# Power_supply.net
KiCad netlist of a schematic drawn in Altium Designer
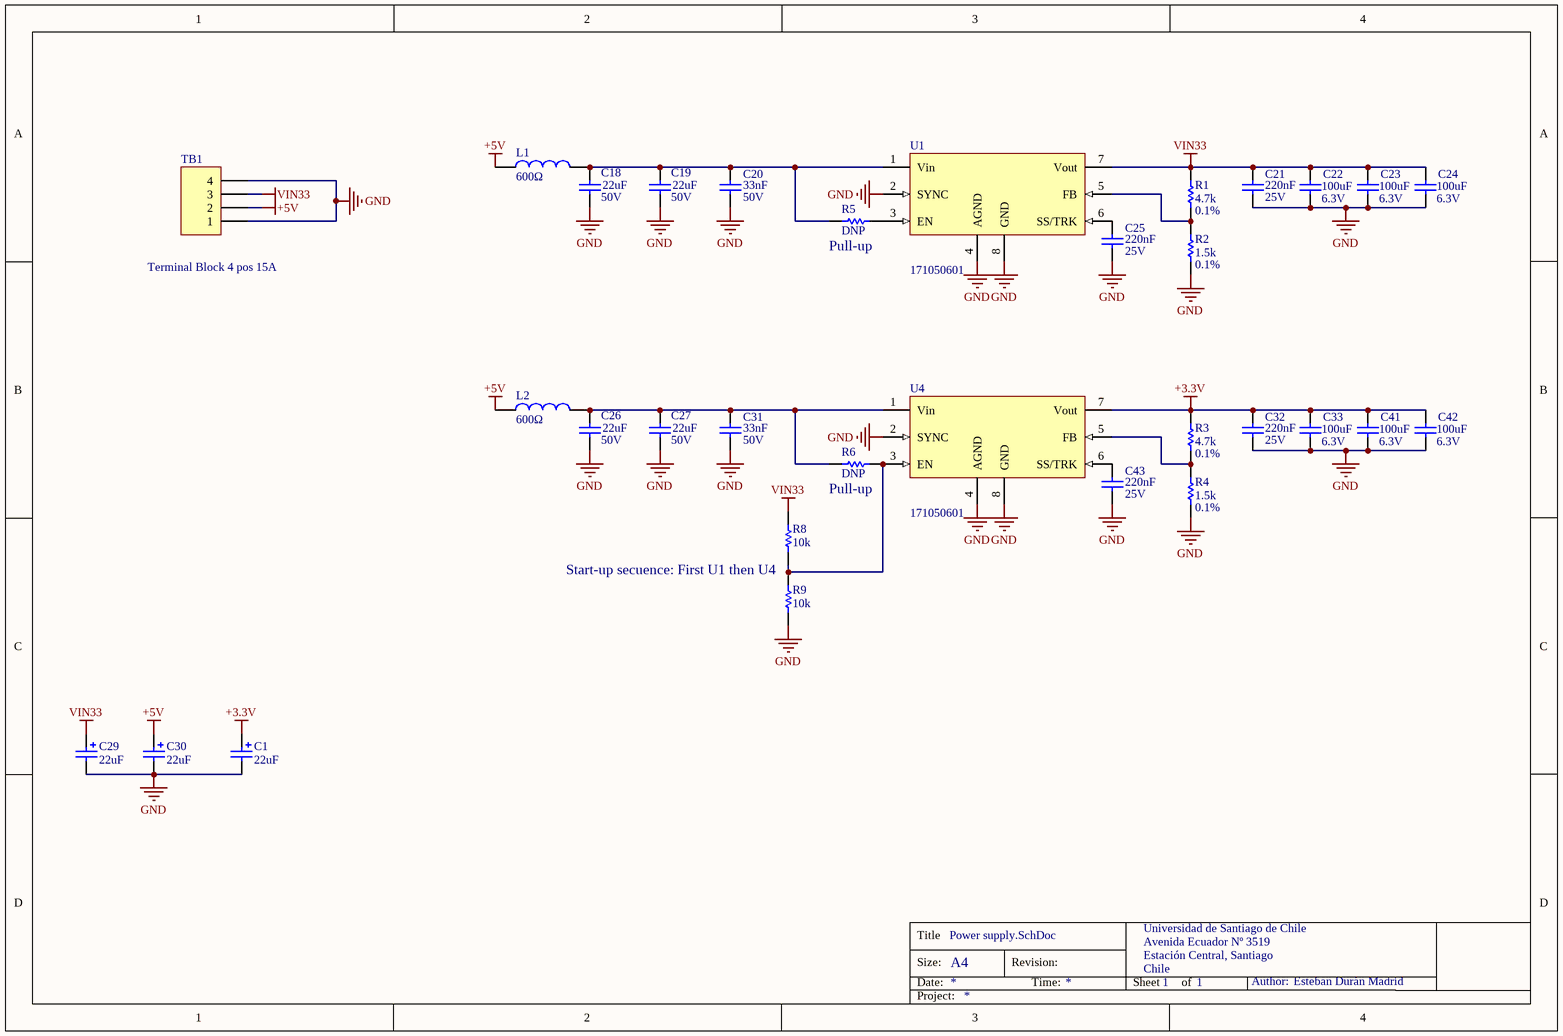
[diagram p0: Power supply.SchDoc]

(export (version "E")
  (design (tool "Eeschema 10.0.6"))
  (components
    (comp (ref "C1")
      (value "22uF")
      (footprint "CAP Electrolítico Radial SMD2")
      (description "Polarized Capacitor (Radial)")
      (fields (field (name "PUBLISHER") "Altium Limited"))
      (libsource (lib "Componentes_SOC") (part "Cap Pol"))
    )
    (comp (ref "C18")
      (value "22uF")
      (footprint "RES_1206")
      (description "Capacitor")
      (fields (field (name "VOLTAGE") "50V") (field (name "PUBLISHER") "Altium Limited"))
      (libsource (lib "Componentes_SOC") (part "Cap_1206"))
    )
    (comp (ref "C19")
      (value "22uF")
      (footprint "RES_1206")
      (description "Capacitor")
      (fields (field (name "VOLTAGE") "50V") (field (name "PUBLISHER") "Altium Limited"))
      (libsource (lib "Componentes_SOC") (part "Cap_1206"))
    )
    (comp (ref "C20")
      (value "33nF")
      (footprint "CAP_0603")
      (description "Capacitor")
      (fields (field (name "VOLTAGE") "50V") (field (name "PUBLISHER") "Altium Limited"))
      (libsource (lib "Componentes_SOC") (part "Cap_0603"))
    )
    (comp (ref "C21")
      (value "220nF")
      (footprint "CAP_0603")
      (description "Capacitor")
      (fields (field (name "VOLTAGE") "25V") (field (name "PUBLISHER") "Altium Limited"))
      (libsource (lib "Componentes_SOC") (part "Cap_0603"))
    )
    (comp (ref "C22")
      (value "100uF")
      (footprint "Cap_1210")
      (description "Capacitor")
      (fields (field (name "VOLTAGE") "6.3V") (field (name "PUBLISHER") "Altium Limited"))
      (libsource (lib "Componentes_SOC") (part "Cap_1210"))
    )
    (comp (ref "C23")
      (value "100uF")
      (footprint "Cap_1210")
      (description "Capacitor")
      (fields (field (name "VOLTAGE") "6.3V") (field (name "PUBLISHER") "Altium Limited"))
      (libsource (lib "Componentes_SOC") (part "Cap_1210"))
    )
    (comp (ref "C24")
      (value "100uF")
      (footprint "Cap_1210")
      (description "Capacitor")
      (fields (field (name "VOLTAGE") "6.3V") (field (name "PUBLISHER") "Altium Limited"))
      (libsource (lib "Componentes_SOC") (part "Cap_1210"))
    )
    (comp (ref "C25")
      (value "220nF")
      (footprint "CAP_0603")
      (description "Capacitor")
      (fields (field (name "VOLTAGE") "25V") (field (name "PUBLISHER") "Altium Limited"))
      (libsource (lib "Componentes_SOC") (part "Cap_0603"))
    )
    (comp (ref "C26")
      (value "22uF")
      (footprint "RES_1206")
      (description "Capacitor")
      (fields (field (name "VOLTAGE") "50V") (field (name "PUBLISHER") "Altium Limited"))
      (libsource (lib "Componentes_SOC") (part "Cap_1206"))
    )
    (comp (ref "C27")
      (value "22uF")
      (footprint "RES_1206")
      (description "Capacitor")
      (fields (field (name "VOLTAGE") "50V") (field (name "PUBLISHER") "Altium Limited"))
      (libsource (lib "Componentes_SOC") (part "Cap_1206"))
    )
    (comp (ref "C29")
      (value "22uF")
      (footprint "CAP Electrolítico Radial SMD2")
      (description "Polarized Capacitor (Radial)")
      (fields (field (name "PUBLISHER") "Altium Limited"))
      (libsource (lib "Componentes_SOC") (part "Cap Pol"))
    )
    (comp (ref "C30")
      (value "22uF")
      (footprint "CAP Electrolítico Radial SMD2")
      (description "Polarized Capacitor (Radial)")
      (fields (field (name "PUBLISHER") "Altium Limited"))
      (libsource (lib "Componentes_SOC") (part "Cap Pol"))
    )
    (comp (ref "C31")
      (value "33nF")
      (footprint "CAP_0603")
      (description "Capacitor")
      (fields (field (name "VOLTAGE") "50V") (field (name "PUBLISHER") "Altium Limited"))
      (libsource (lib "Componentes_SOC") (part "Cap_0603"))
    )
    (comp (ref "C32")
      (value "220nF")
      (footprint "CAP_0603")
      (description "Capacitor")
      (fields (field (name "VOLTAGE") "25V") (field (name "PUBLISHER") "Altium Limited"))
      (libsource (lib "Componentes_SOC") (part "Cap_0603"))
    )
    (comp (ref "C33")
      (value "100uF")
      (footprint "Cap_1210")
      (description "Capacitor")
      (fields (field (name "VOLTAGE") "6.3V") (field (name "PUBLISHER") "Altium Limited"))
      (libsource (lib "Componentes_SOC") (part "Cap_1210"))
    )
    (comp (ref "C41")
      (value "100uF")
      (footprint "Cap_1210")
      (description "Capacitor")
      (fields (field (name "VOLTAGE") "6.3V") (field (name "PUBLISHER") "Altium Limited"))
      (libsource (lib "Componentes_SOC") (part "Cap_1210"))
    )
    (comp (ref "C42")
      (value "100uF")
      (footprint "Cap_1210")
      (description "Capacitor")
      (fields (field (name "VOLTAGE") "6.3V") (field (name "PUBLISHER") "Altium Limited"))
      (libsource (lib "Componentes_SOC") (part "Cap_1210"))
    )
    (comp (ref "C43")
      (value "220nF")
      (footprint "CAP_0603")
      (description "Capacitor")
      (fields (field (name "VOLTAGE") "25V") (field (name "PUBLISHER") "Altium Limited"))
      (libsource (lib "Componentes_SOC") (part "Cap_0603"))
    )
    (comp (ref "L1")
      (value "600Ω")
      (footprint "WE-CBF_0805_High Current")
      (description "WE-CBF SMD EMI Suppression Ferrite Bead, 0805, 600Ω")
      (fields
        (field (name "PARTNUMBER") "742792040")
        (field (name "PUBLISHER") "Wurth Elektronik")
        (field (name "CREATED") "2018_09_11_AGeiger")
      )
      (libsource (lib "UltraZOhm_CarrierBoard_1v1") (part "WE-CBF, 742792040"))
    )
    (comp (ref "L2")
      (value "600Ω")
      (footprint "WE-CBF_0805_High Current")
      (description "WE-CBF SMD EMI Suppression Ferrite Bead, 0805, 600Ω")
      (fields
        (field (name "PARTNUMBER") "742792040")
        (field (name "PUBLISHER") "Wurth Elektronik")
        (field (name "CREATED") "2018_09_11_AGeiger")
      )
      (libsource (lib "UltraZOhm_CarrierBoard_1v1") (part "WE-CBF, 742792040"))
    )
    (comp (ref "R1")
      (value "4.7k")
      (footprint "RES_0603")
      (fields (field (name "TOLERANCE") "0.1%") (field (name "PUBLISHER") "Altium Limited"))
      (libsource (lib "Componentes_SOC") (part "Res0603"))
    )
    (comp (ref "R2")
      (value "1.5k")
      (footprint "RES_0603")
      (fields (field (name "TOLERANCE") "0.1%") (field (name "PUBLISHER") "Altium Limited"))
      (libsource (lib "Componentes_SOC") (part "Res0603"))
    )
    (comp (ref "R3")
      (value "4.7k")
      (footprint "RES_0603")
      (fields (field (name "TOLERANCE") "0.1%") (field (name "PUBLISHER") "Altium Limited"))
      (libsource (lib "Componentes_SOC") (part "Res0603"))
    )
    (comp (ref "R4")
      (value "1.5k")
      (footprint "RES_0603")
      (fields (field (name "TOLERANCE") "0.1%") (field (name "PUBLISHER") "Altium Limited"))
      (libsource (lib "Componentes_SOC") (part "Res0603"))
    )
    (comp (ref "R5")
      (value "DNP")
      (footprint "RES_0603")
      (fields (field (name "PUBLISHER") "Altium Limited"))
      (libsource (lib "Componentes_SOC") (part "Res0603"))
    )
    (comp (ref "R6")
      (value "DNP")
      (footprint "RES_0603")
      (fields (field (name "PUBLISHER") "Altium Limited"))
      (libsource (lib "Componentes_SOC") (part "Res0603"))
    )
    (comp (ref "R8")
      (value "10k")
      (footprint "RES_0603")
      (fields (field (name "PUBLISHER") "Altium Limited"))
      (libsource (lib "Componentes_SOC") (part "Res0603"))
    )
    (comp (ref "R9")
      (value "10k")
      (footprint "RES_0603")
      (fields (field (name "PUBLISHER") "Altium Limited"))
      (libsource (lib "Componentes_SOC") (part "Res0603"))
    )
    (comp (ref "TB1")
      (value "Terminal Block 4 pos 15A")
      (footprint "Terminal Block 4 pos 15A")
      (description "Molex Through Hole")
      (fields (field (name "PUBLISHER") "Altium Limited"))
      (libsource (lib "Componentes_SOC") (part "Terminal Block 4 pos 15A"))
    )
    (comp (ref "U1")
      (value "171050601")
      (footprint "7TO-PMOD")
      (description "DC/DC VIN = 6V-36V, 5A, VOUT = 0.8V-6V")
      (fields (field (name "MANUFACTURER") "Wuerth Elektronik") (field (name "CREATED") "2018_09_06_AGeiger"))
      (libsource (lib "UltraZOhm_CarrierBoard_1v1") (part "WE-DCDC-171050601"))
    )
    (comp (ref "U4")
      (value "171050601")
      (footprint "7TO-PMOD")
      (description "DC/DC VIN = 6V-36V, 5A, VOUT = 0.8V-6V")
      (fields (field (name "MANUFACTURER") "Wuerth Elektronik") (field (name "CREATED") "2018_09_06_AGeiger"))
      (libsource (lib "UltraZOhm_CarrierBoard_1v1") (part "WE-DCDC-171050601"))
    )
  )
  (nets
    (net (code "1") (name "+3.3V") (class "Default")
      (node (ref "C1") (pin "1") (pinfunction "1_1") (pintype "passive"))
      (node (ref "C32") (pin "1") (pinfunction "1_1") (pintype "passive"))
      (node (ref "C33") (pin "1") (pinfunction "1_1") (pintype "passive"))
      (node (ref "C41") (pin "1") (pinfunction "1_1") (pintype "passive"))
      (node (ref "C42") (pin "1") (pinfunction "1_1") (pintype "passive"))
      (node (ref "R3") (pin "2") (pinfunction "2_2") (pintype "passive"))
      (node (ref "U4") (pin "7") (pinfunction "Vout_7") (pintype "power_in"))
    )
    (net (code "2") (name "+5V") (class "Default")
      (node (ref "C30") (pin "1") (pinfunction "1_1") (pintype "passive"))
      (node (ref "L1") (pin "1") (pinfunction "1_1") (pintype "passive"))
      (node (ref "L2") (pin "1") (pinfunction "1_1") (pintype "passive"))
      (node (ref "TB1") (pin "2") (pinfunction "2_2") (pintype "passive"))
    )
    (net (code "3") (name "GND") (class "Default")
      (node (ref "C1") (pin "2") (pinfunction "2_2") (pintype "passive"))
      (node (ref "C18") (pin "2") (pinfunction "2_2") (pintype "passive"))
      (node (ref "C19") (pin "2") (pinfunction "2_2") (pintype "passive"))
      (node (ref "C20") (pin "2") (pinfunction "2_2") (pintype "passive"))
      (node (ref "C21") (pin "2") (pinfunction "2_2") (pintype "passive"))
      (node (ref "C22") (pin "2") (pinfunction "2_2") (pintype "passive"))
      (node (ref "C23") (pin "2") (pinfunction "2_2") (pintype "passive"))
      (node (ref "C24") (pin "2") (pinfunction "2_2") (pintype "passive"))
      (node (ref "C25") (pin "2") (pinfunction "2_2") (pintype "passive"))
      (node (ref "C26") (pin "2") (pinfunction "2_2") (pintype "passive"))
      (node (ref "C27") (pin "2") (pinfunction "2_2") (pintype "passive"))
      (node (ref "C29") (pin "2") (pinfunction "2_2") (pintype "passive"))
      (node (ref "C30") (pin "2") (pinfunction "2_2") (pintype "passive"))
      (node (ref "C31") (pin "2") (pinfunction "2_2") (pintype "passive"))
      (node (ref "C32") (pin "2") (pinfunction "2_2") (pintype "passive"))
      (node (ref "C33") (pin "2") (pinfunction "2_2") (pintype "passive"))
      (node (ref "C41") (pin "2") (pinfunction "2_2") (pintype "passive"))
      (node (ref "C42") (pin "2") (pinfunction "2_2") (pintype "passive"))
      (node (ref "C43") (pin "2") (pinfunction "2_2") (pintype "passive"))
      (node (ref "R2") (pin "1") (pinfunction "1_1") (pintype "passive"))
      (node (ref "R4") (pin "1") (pinfunction "1_1") (pintype "passive"))
      (node (ref "R9") (pin "1") (pinfunction "1_1") (pintype "passive"))
      (node (ref "TB1") (pin "1") (pinfunction "1_1") (pintype "passive"))
      (node (ref "TB1") (pin "4") (pinfunction "4_4") (pintype "passive"))
      (node (ref "U1") (pin "2") (pinfunction "SYNC_2") (pintype "input"))
      (node (ref "U1") (pin "4") (pinfunction "AGND_4") (pintype "power_in"))
      (node (ref "U1") (pin "8") (pinfunction "GND_8") (pintype "power_in"))
      (node (ref "U4") (pin "2") (pinfunction "SYNC_2") (pintype "input"))
      (node (ref "U4") (pin "4") (pinfunction "AGND_4") (pintype "power_in"))
      (node (ref "U4") (pin "8") (pinfunction "GND_8") (pintype "power_in"))
    )
    (net (code "4") (name "Net-(U1-EN)") (class "Default")
      (node (ref "R5") (pin "1") (pinfunction "1_1") (pintype "passive"))
      (node (ref "U1") (pin "3") (pinfunction "EN_3") (pintype "input"))
    )
    (net (code "5") (name "Net-(U1-FB)") (class "Default")
      (node (ref "R1") (pin "1") (pinfunction "1_1") (pintype "passive"))
      (node (ref "R2") (pin "2") (pinfunction "2_2") (pintype "passive"))
      (node (ref "U1") (pin "5") (pinfunction "FB_5") (pintype "input"))
    )
    (net (code "6") (name "Net-(U1-SS{slash}TRK)") (class "Default")
      (node (ref "C25") (pin "1") (pinfunction "1_1") (pintype "passive"))
      (node (ref "U1") (pin "6") (pinfunction "SS/TRK_6") (pintype "input"))
    )
    (net (code "7") (name "Net-(U1-Vin)") (class "Default")
      (node (ref "C18") (pin "1") (pinfunction "1_1") (pintype "passive"))
      (node (ref "C19") (pin "1") (pinfunction "1_1") (pintype "passive"))
      (node (ref "C20") (pin "1") (pinfunction "1_1") (pintype "passive"))
      (node (ref "L1") (pin "2") (pinfunction "2_2") (pintype "passive"))
      (node (ref "R5") (pin "2") (pinfunction "2_2") (pintype "passive"))
      (node (ref "U1") (pin "1") (pinfunction "Vin_1") (pintype "power_in"))
    )
    (net (code "8") (name "Net-(U4-EN)") (class "Default")
      (node (ref "R6") (pin "1") (pinfunction "1_1") (pintype "passive"))
      (node (ref "R8") (pin "2") (pinfunction "2_2") (pintype "passive"))
      (node (ref "R9") (pin "2") (pinfunction "2_2") (pintype "passive"))
      (node (ref "U4") (pin "3") (pinfunction "EN_3") (pintype "input"))
    )
    (net (code "9") (name "Net-(U4-FB)") (class "Default")
      (node (ref "R3") (pin "1") (pinfunction "1_1") (pintype "passive"))
      (node (ref "R4") (pin "2") (pinfunction "2_2") (pintype "passive"))
      (node (ref "U4") (pin "5") (pinfunction "FB_5") (pintype "input"))
    )
    (net (code "10") (name "Net-(U4-SS{slash}TRK)") (class "Default")
      (node (ref "C43") (pin "1") (pinfunction "1_1") (pintype "passive"))
      (node (ref "U4") (pin "6") (pinfunction "SS/TRK_6") (pintype "input"))
    )
    (net (code "11") (name "Net-(U4-Vin)") (class "Default")
      (node (ref "C26") (pin "1") (pinfunction "1_1") (pintype "passive"))
      (node (ref "C27") (pin "1") (pinfunction "1_1") (pintype "passive"))
      (node (ref "C31") (pin "1") (pinfunction "1_1") (pintype "passive"))
      (node (ref "L2") (pin "2") (pinfunction "2_2") (pintype "passive"))
      (node (ref "R6") (pin "2") (pinfunction "2_2") (pintype "passive"))
      (node (ref "U4") (pin "1") (pinfunction "Vin_1") (pintype "power_in"))
    )
    (net (code "12") (name "VIN33") (class "Default")
      (node (ref "C21") (pin "1") (pinfunction "1_1") (pintype "passive"))
      (node (ref "C22") (pin "1") (pinfunction "1_1") (pintype "passive"))
      (node (ref "C23") (pin "1") (pinfunction "1_1") (pintype "passive"))
      (node (ref "C24") (pin "1") (pinfunction "1_1") (pintype "passive"))
      (node (ref "C29") (pin "1") (pinfunction "1_1") (pintype "passive"))
      (node (ref "R1") (pin "2") (pinfunction "2_2") (pintype "passive"))
      (node (ref "R8") (pin "1") (pinfunction "1_1") (pintype "passive"))
      (node (ref "TB1") (pin "3") (pinfunction "3_3") (pintype "passive"))
      (node (ref "U1") (pin "7") (pinfunction "Vout_7") (pintype "power_in"))
    )
  )
)
